# Insoladora.net
KiCad netlist of a schematic drawn in Altium Designer
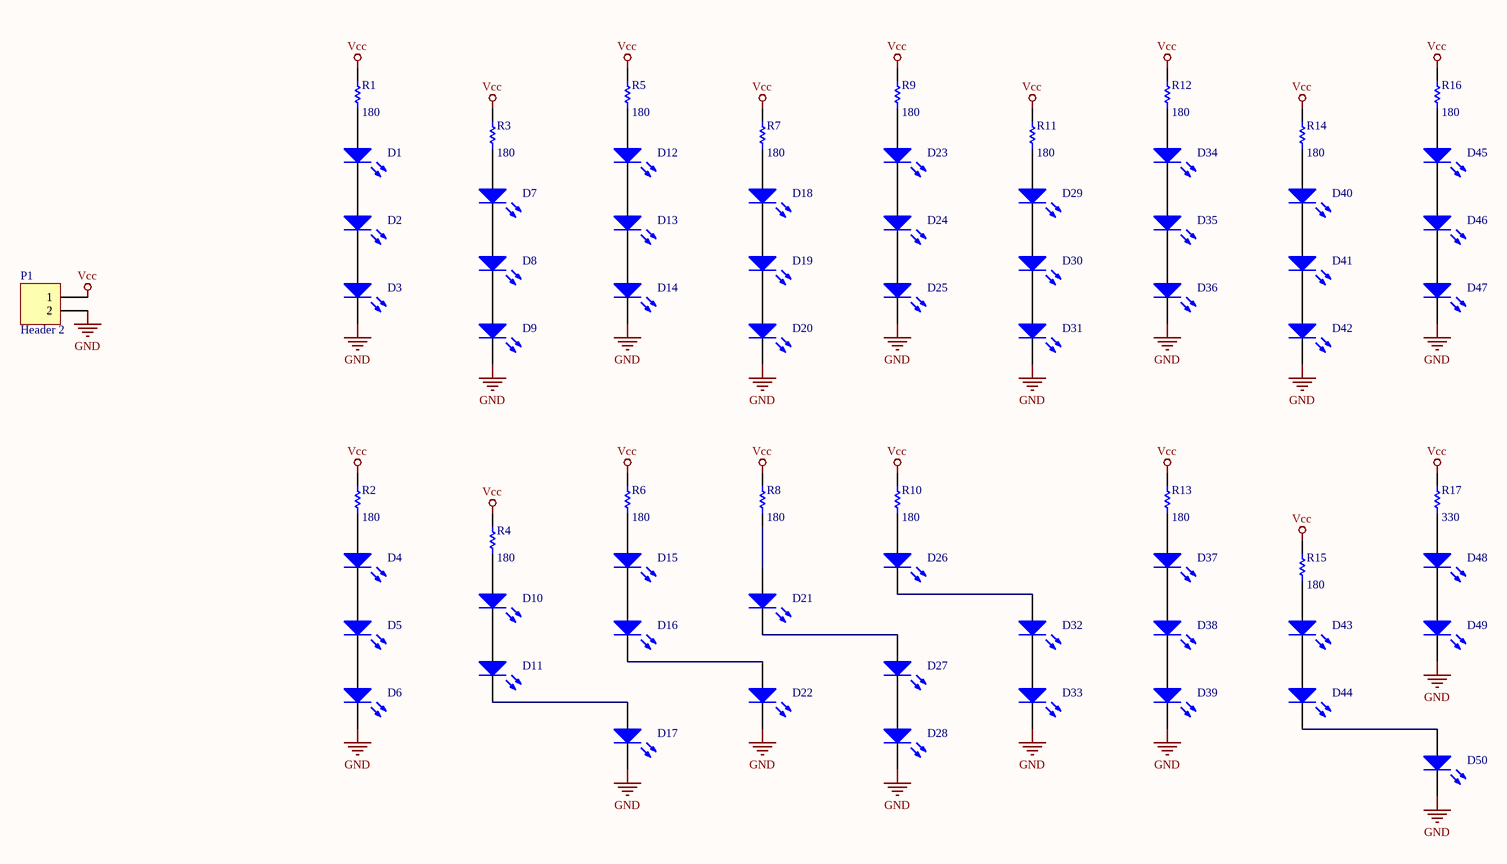
[diagram p0: Insoladora.SchDoc]

(export (version "E")
  (design (tool "Eeschema 10.0.6"))
  (components
    (comp (ref "D1")
      (value "LEDUV")
      (footprint "LED Clear")
      (description "LED UV 5mm 25° apertura")
      (fields (field (name "PUBLISHER") "Altium Limited"))
      (libsource (lib "Miscellaneous Devices") (part "LED2"))
    )
    (comp (ref "D2")
      (value "LEDUV")
      (footprint "LED Clear")
      (description "LED UV 5mm 25° apertura")
      (fields (field (name "PUBLISHER") "Altium Limited"))
      (libsource (lib "Miscellaneous Devices") (part "LED2"))
    )
    (comp (ref "D3")
      (value "LEDUV")
      (footprint "LED Clear")
      (description "LED UV 5mm 25° apertura")
      (fields (field (name "PUBLISHER") "Altium Limited"))
      (libsource (lib "Miscellaneous Devices") (part "LED2"))
    )
    (comp (ref "D4")
      (value "LEDUV")
      (footprint "LED Clear")
      (description "LED UV 5mm 25° apertura")
      (fields (field (name "PUBLISHER") "Altium Limited"))
      (libsource (lib "Miscellaneous Devices") (part "LED2"))
    )
    (comp (ref "D5")
      (value "LEDUV")
      (footprint "LED Clear")
      (description "LED UV 5mm 25° apertura")
      (fields (field (name "PUBLISHER") "Altium Limited"))
      (libsource (lib "Miscellaneous Devices") (part "LED2"))
    )
    (comp (ref "D6")
      (value "LEDUV")
      (footprint "LED Clear")
      (description "LED UV 5mm 25° apertura")
      (fields (field (name "PUBLISHER") "Altium Limited"))
      (libsource (lib "Miscellaneous Devices") (part "LED2"))
    )
    (comp (ref "D7")
      (value "LEDUV")
      (footprint "LED Clear")
      (description "LED UV 5mm 25° apertura")
      (fields (field (name "PUBLISHER") "Altium Limited"))
      (libsource (lib "Miscellaneous Devices") (part "LED2"))
    )
    (comp (ref "D8")
      (value "LEDUV")
      (footprint "LED Clear")
      (description "LED UV 5mm 25° apertura")
      (fields (field (name "PUBLISHER") "Altium Limited"))
      (libsource (lib "Miscellaneous Devices") (part "LED2"))
    )
    (comp (ref "D9")
      (value "LEDUV")
      (footprint "LED Clear")
      (description "LED UV 5mm 25° apertura")
      (fields (field (name "PUBLISHER") "Altium Limited"))
      (libsource (lib "Miscellaneous Devices") (part "LED2"))
    )
    (comp (ref "D10")
      (value "LEDUV")
      (footprint "LED Clear")
      (description "LED UV 5mm 25° apertura")
      (fields (field (name "PUBLISHER") "Altium Limited"))
      (libsource (lib "Miscellaneous Devices") (part "LED2"))
    )
    (comp (ref "D11")
      (value "LEDUV")
      (footprint "LED Clear")
      (description "LED UV 5mm 25° apertura")
      (fields (field (name "PUBLISHER") "Altium Limited"))
      (libsource (lib "Miscellaneous Devices") (part "LED2"))
    )
    (comp (ref "D12")
      (value "LEDUV")
      (footprint "LED Clear")
      (description "LED UV 5mm 25° apertura")
      (fields (field (name "PUBLISHER") "Altium Limited"))
      (libsource (lib "Miscellaneous Devices") (part "LED2"))
    )
    (comp (ref "D13")
      (value "LEDUV")
      (footprint "LED Clear")
      (description "LED UV 5mm 25° apertura")
      (fields (field (name "PUBLISHER") "Altium Limited"))
      (libsource (lib "Miscellaneous Devices") (part "LED2"))
    )
    (comp (ref "D14")
      (value "LEDUV")
      (footprint "LED Clear")
      (description "LED UV 5mm 25° apertura")
      (fields (field (name "PUBLISHER") "Altium Limited"))
      (libsource (lib "Miscellaneous Devices") (part "LED2"))
    )
    (comp (ref "D15")
      (value "LEDUV")
      (footprint "LED Clear")
      (description "LED UV 5mm 25° apertura")
      (fields (field (name "PUBLISHER") "Altium Limited"))
      (libsource (lib "Miscellaneous Devices") (part "LED2"))
    )
    (comp (ref "D16")
      (value "LEDUV")
      (footprint "LED Clear")
      (description "LED UV 5mm 25° apertura")
      (fields (field (name "PUBLISHER") "Altium Limited"))
      (libsource (lib "Miscellaneous Devices") (part "LED2"))
    )
    (comp (ref "D17")
      (value "LEDUV")
      (footprint "LED Clear")
      (description "LED UV 5mm 25° apertura")
      (fields (field (name "PUBLISHER") "Altium Limited"))
      (libsource (lib "Miscellaneous Devices") (part "LED2"))
    )
    (comp (ref "D18")
      (value "LEDUV")
      (footprint "LED Clear")
      (description "LED UV 5mm 25° apertura")
      (fields (field (name "PUBLISHER") "Altium Limited"))
      (libsource (lib "Miscellaneous Devices") (part "LED2"))
    )
    (comp (ref "D19")
      (value "LEDUV")
      (footprint "LED Clear")
      (description "LED UV 5mm 25° apertura")
      (fields (field (name "PUBLISHER") "Altium Limited"))
      (libsource (lib "Miscellaneous Devices") (part "LED2"))
    )
    (comp (ref "D20")
      (value "LEDUV")
      (footprint "LED Clear")
      (description "LED UV 5mm 25° apertura")
      (fields (field (name "PUBLISHER") "Altium Limited"))
      (libsource (lib "Miscellaneous Devices") (part "LED2"))
    )
    (comp (ref "D21")
      (value "LEDUV")
      (footprint "LED Clear")
      (description "LED UV 5mm 25° apertura")
      (fields (field (name "PUBLISHER") "Altium Limited"))
      (libsource (lib "Miscellaneous Devices") (part "LED2"))
    )
    (comp (ref "D22")
      (value "LEDUV")
      (footprint "LED Clear")
      (description "LED UV 5mm 25° apertura")
      (fields (field (name "PUBLISHER") "Altium Limited"))
      (libsource (lib "Miscellaneous Devices") (part "LED2"))
    )
    (comp (ref "D23")
      (value "LEDUV")
      (footprint "LED Clear")
      (description "LED UV 5mm 25° apertura")
      (fields (field (name "PUBLISHER") "Altium Limited"))
      (libsource (lib "Miscellaneous Devices") (part "LED2"))
    )
    (comp (ref "D24")
      (value "LEDUV")
      (footprint "LED Clear")
      (description "LED UV 5mm 25° apertura")
      (fields (field (name "PUBLISHER") "Altium Limited"))
      (libsource (lib "Miscellaneous Devices") (part "LED2"))
    )
    (comp (ref "D25")
      (value "LEDUV")
      (footprint "LED Clear")
      (description "LED UV 5mm 25° apertura")
      (fields (field (name "PUBLISHER") "Altium Limited"))
      (libsource (lib "Miscellaneous Devices") (part "LED2"))
    )
    (comp (ref "D26")
      (value "LEDUV")
      (footprint "LED Clear")
      (description "LED UV 5mm 25° apertura")
      (fields (field (name "PUBLISHER") "Altium Limited"))
      (libsource (lib "Miscellaneous Devices") (part "LED2"))
    )
    (comp (ref "D27")
      (value "LEDUV")
      (footprint "LED Clear")
      (description "LED UV 5mm 25° apertura")
      (fields (field (name "PUBLISHER") "Altium Limited"))
      (libsource (lib "Miscellaneous Devices") (part "LED2"))
    )
    (comp (ref "D28")
      (value "LEDUV")
      (footprint "LED Clear")
      (description "LED UV 5mm 25° apertura")
      (fields (field (name "PUBLISHER") "Altium Limited"))
      (libsource (lib "Miscellaneous Devices") (part "LED2"))
    )
    (comp (ref "D29")
      (value "LEDUV")
      (footprint "LED Clear")
      (description "LED UV 5mm 25° apertura")
      (fields (field (name "PUBLISHER") "Altium Limited"))
      (libsource (lib "Miscellaneous Devices") (part "LED2"))
    )
    (comp (ref "D30")
      (value "LEDUV")
      (footprint "LED Clear")
      (description "LED UV 5mm 25° apertura")
      (fields (field (name "PUBLISHER") "Altium Limited"))
      (libsource (lib "Miscellaneous Devices") (part "LED2"))
    )
    (comp (ref "D31")
      (value "LEDUV")
      (footprint "LED Clear")
      (description "LED UV 5mm 25° apertura")
      (fields (field (name "PUBLISHER") "Altium Limited"))
      (libsource (lib "Miscellaneous Devices") (part "LED2"))
    )
    (comp (ref "D32")
      (value "LEDUV")
      (footprint "LED Clear")
      (description "LED UV 5mm 25° apertura")
      (fields (field (name "PUBLISHER") "Altium Limited"))
      (libsource (lib "Miscellaneous Devices") (part "LED2"))
    )
    (comp (ref "D33")
      (value "LEDUV")
      (footprint "LED Clear")
      (description "LED UV 5mm 25° apertura")
      (fields (field (name "PUBLISHER") "Altium Limited"))
      (libsource (lib "Miscellaneous Devices") (part "LED2"))
    )
    (comp (ref "D34")
      (value "LEDUV")
      (footprint "LED Clear")
      (description "LED UV 5mm 25° apertura")
      (fields (field (name "PUBLISHER") "Altium Limited"))
      (libsource (lib "Miscellaneous Devices") (part "LED2"))
    )
    (comp (ref "D35")
      (value "LEDUV")
      (footprint "LED Clear")
      (description "LED UV 5mm 25° apertura")
      (fields (field (name "PUBLISHER") "Altium Limited"))
      (libsource (lib "Miscellaneous Devices") (part "LED2"))
    )
    (comp (ref "D36")
      (value "LEDUV")
      (footprint "LED Clear")
      (description "LED UV 5mm 25° apertura")
      (fields (field (name "PUBLISHER") "Altium Limited"))
      (libsource (lib "Miscellaneous Devices") (part "LED2"))
    )
    (comp (ref "D37")
      (value "LEDUV")
      (footprint "LED Clear")
      (description "LED UV 5mm 25° apertura")
      (fields (field (name "PUBLISHER") "Altium Limited"))
      (libsource (lib "Miscellaneous Devices") (part "LED2"))
    )
    (comp (ref "D38")
      (value "LEDUV")
      (footprint "LED Clear")
      (description "LED UV 5mm 25° apertura")
      (fields (field (name "PUBLISHER") "Altium Limited"))
      (libsource (lib "Miscellaneous Devices") (part "LED2"))
    )
    (comp (ref "D39")
      (value "LEDUV")
      (footprint "LED Clear")
      (description "LED UV 5mm 25° apertura")
      (fields (field (name "PUBLISHER") "Altium Limited"))
      (libsource (lib "Miscellaneous Devices") (part "LED2"))
    )
    (comp (ref "D40")
      (value "LEDUV")
      (footprint "LED Clear")
      (description "LED UV 5mm 25° apertura")
      (fields (field (name "PUBLISHER") "Altium Limited"))
      (libsource (lib "Miscellaneous Devices") (part "LED2"))
    )
    (comp (ref "D41")
      (value "LEDUV")
      (footprint "LED Clear")
      (description "LED UV 5mm 25° apertura")
      (fields (field (name "PUBLISHER") "Altium Limited"))
      (libsource (lib "Miscellaneous Devices") (part "LED2"))
    )
    (comp (ref "D42")
      (value "LEDUV")
      (footprint "LED Clear")
      (description "LED UV 5mm 25° apertura")
      (fields (field (name "PUBLISHER") "Altium Limited"))
      (libsource (lib "Miscellaneous Devices") (part "LED2"))
    )
    (comp (ref "D43")
      (value "LEDUV")
      (footprint "LED Clear")
      (description "LED UV 5mm 25° apertura")
      (fields (field (name "PUBLISHER") "Altium Limited"))
      (libsource (lib "Miscellaneous Devices") (part "LED2"))
    )
    (comp (ref "D44")
      (value "LEDUV")
      (footprint "LED Clear")
      (description "LED UV 5mm 25° apertura")
      (fields (field (name "PUBLISHER") "Altium Limited"))
      (libsource (lib "Miscellaneous Devices") (part "LED2"))
    )
    (comp (ref "D45")
      (value "LEDUV")
      (footprint "LED Clear")
      (description "LED UV 5mm 25° apertura")
      (fields (field (name "PUBLISHER") "Altium Limited"))
      (libsource (lib "Miscellaneous Devices") (part "LED2"))
    )
    (comp (ref "D46")
      (value "LEDUV")
      (footprint "LED Clear")
      (description "LED UV 5mm 25° apertura")
      (fields (field (name "PUBLISHER") "Altium Limited"))
      (libsource (lib "Miscellaneous Devices") (part "LED2"))
    )
    (comp (ref "D47")
      (value "LEDUV")
      (footprint "LED Clear")
      (description "LED UV 5mm 25° apertura")
      (fields (field (name "PUBLISHER") "Altium Limited"))
      (libsource (lib "Miscellaneous Devices") (part "LED2"))
    )
    (comp (ref "D48")
      (value "LEDUV")
      (footprint "LED Clear")
      (description "LED UV 5mm 25° apertura")
      (fields (field (name "PUBLISHER") "Altium Limited"))
      (libsource (lib "Miscellaneous Devices") (part "LED2"))
    )
    (comp (ref "D49")
      (value "LEDUV")
      (footprint "LED Clear")
      (description "LED UV 5mm 25° apertura")
      (fields (field (name "PUBLISHER") "Altium Limited"))
      (libsource (lib "Miscellaneous Devices") (part "LED2"))
    )
    (comp (ref "D50")
      (value "LEDUV")
      (footprint "LED Clear")
      (description "LED UV 5mm 25° apertura")
      (fields (field (name "PUBLISHER") "Altium Limited"))
      (libsource (lib "Miscellaneous Devices") (part "LED2"))
    )
    (comp (ref "P1")
      (value "Header 2")
      (footprint "HEADER 2")
      (description "Header, 2-Pin")
      (fields (field (name "PUBLISHER") "Altium Limited"))
      (libsource (lib "Miscellaneous Connectors") (part "Header 2"))
    )
    (comp (ref "R1")
      (value "180")
      (description "Resistor")
      (fields (field (name "Comment") "Res1") (field (name "PUBLISHER") "Altium Limited"))
      (libsource (lib "Miscellaneous Devices") (part "Res1"))
    )
    (comp (ref "R2")
      (value "180")
      (description "Resistor")
      (fields (field (name "Comment") "Res1") (field (name "PUBLISHER") "Altium Limited"))
      (libsource (lib "Miscellaneous Devices") (part "Res1"))
    )
    (comp (ref "R3")
      (value "180")
      (description "Resistor")
      (fields (field (name "Comment") "Res1") (field (name "PUBLISHER") "Altium Limited"))
      (libsource (lib "Miscellaneous Devices") (part "Res1"))
    )
    (comp (ref "R4")
      (value "180")
      (description "Resistor")
      (fields (field (name "Comment") "Res1") (field (name "PUBLISHER") "Altium Limited"))
      (libsource (lib "Miscellaneous Devices") (part "Res1"))
    )
    (comp (ref "R5")
      (value "180")
      (description "Resistor")
      (fields (field (name "Comment") "Res1") (field (name "PUBLISHER") "Altium Limited"))
      (libsource (lib "Miscellaneous Devices") (part "Res1"))
    )
    (comp (ref "R6")
      (value "180")
      (description "Resistor")
      (fields (field (name "Comment") "Res1") (field (name "PUBLISHER") "Altium Limited"))
      (libsource (lib "Miscellaneous Devices") (part "Res1"))
    )
    (comp (ref "R7")
      (value "180")
      (description "Resistor")
      (fields (field (name "Comment") "Res1") (field (name "PUBLISHER") "Altium Limited"))
      (libsource (lib "Miscellaneous Devices") (part "Res1"))
    )
    (comp (ref "R8")
      (value "180")
      (description "Resistor")
      (fields (field (name "Comment") "Res1") (field (name "PUBLISHER") "Altium Limited"))
      (libsource (lib "Miscellaneous Devices") (part "Res1"))
    )
    (comp (ref "R9")
      (value "180")
      (description "Resistor")
      (fields (field (name "Comment") "Res1") (field (name "PUBLISHER") "Altium Limited"))
      (libsource (lib "Miscellaneous Devices") (part "Res1"))
    )
    (comp (ref "R10")
      (value "180")
      (description "Resistor")
      (fields (field (name "Comment") "Res1") (field (name "PUBLISHER") "Altium Limited"))
      (libsource (lib "Miscellaneous Devices") (part "Res1"))
    )
    (comp (ref "R11")
      (value "180")
      (description "Resistor")
      (fields (field (name "Comment") "Res1") (field (name "PUBLISHER") "Altium Limited"))
      (libsource (lib "Miscellaneous Devices") (part "Res1"))
    )
    (comp (ref "R12")
      (value "180")
      (description "Resistor")
      (fields (field (name "Comment") "Res1") (field (name "PUBLISHER") "Altium Limited"))
      (libsource (lib "Miscellaneous Devices") (part "Res1"))
    )
    (comp (ref "R13")
      (value "180")
      (description "Resistor")
      (fields (field (name "Comment") "Res1") (field (name "PUBLISHER") "Altium Limited"))
      (libsource (lib "Miscellaneous Devices") (part "Res1"))
    )
    (comp (ref "R14")
      (value "180")
      (description "Resistor")
      (fields (field (name "Comment") "Res1") (field (name "PUBLISHER") "Altium Limited"))
      (libsource (lib "Miscellaneous Devices") (part "Res1"))
    )
    (comp (ref "R15")
      (value "180")
      (description "Resistor")
      (fields (field (name "Comment") "Res1") (field (name "PUBLISHER") "Altium Limited"))
      (libsource (lib "Miscellaneous Devices") (part "Res1"))
    )
    (comp (ref "R16")
      (value "180")
      (description "Resistor")
      (fields (field (name "Comment") "Res1") (field (name "PUBLISHER") "Altium Limited"))
      (libsource (lib "Miscellaneous Devices") (part "Res1"))
    )
    (comp (ref "R17")
      (value "330")
      (description "Resistor")
      (fields (field (name "Comment") "Res1") (field (name "PUBLISHER") "Altium Limited"))
      (libsource (lib "Miscellaneous Devices") (part "Res1"))
    )
  )
  (nets
    (net (code "1") (name "GND") (class "Default")
      (node (ref "D14") (pin "2") (pinfunction "K_2") (pintype "passive"))
      (node (ref "D17") (pin "2") (pinfunction "K_2") (pintype "passive"))
      (node (ref "D20") (pin "2") (pinfunction "K_2") (pintype "passive"))
      (node (ref "D22") (pin "2") (pinfunction "K_2") (pintype "passive"))
      (node (ref "D25") (pin "2") (pinfunction "K_2") (pintype "passive"))
      (node (ref "D28") (pin "2") (pinfunction "K_2") (pintype "passive"))
      (node (ref "D3") (pin "2") (pinfunction "K_2") (pintype "passive"))
      (node (ref "D31") (pin "2") (pinfunction "K_2") (pintype "passive"))
      (node (ref "D33") (pin "2") (pinfunction "K_2") (pintype "passive"))
      (node (ref "D36") (pin "2") (pinfunction "K_2") (pintype "passive"))
      (node (ref "D39") (pin "2") (pinfunction "K_2") (pintype "passive"))
      (node (ref "D42") (pin "2") (pinfunction "K_2") (pintype "passive"))
      (node (ref "D47") (pin "2") (pinfunction "K_2") (pintype "passive"))
      (node (ref "D49") (pin "2") (pinfunction "K_2") (pintype "passive"))
      (node (ref "D50") (pin "2") (pinfunction "K_2") (pintype "passive"))
      (node (ref "D6") (pin "2") (pinfunction "K_2") (pintype "passive"))
      (node (ref "D9") (pin "2") (pinfunction "K_2") (pintype "passive"))
      (node (ref "P1") (pin "2") (pinfunction "2_2") (pintype "passive"))
    )
    (net (code "2") (name "Net-(D1-A)") (class "Default")
      (node (ref "D1") (pin "1") (pinfunction "A_1") (pintype "passive"))
      (node (ref "R1") (pin "1") (pinfunction "1_1") (pintype "passive"))
    )
    (net (code "3") (name "Net-(D1-K)") (class "Default")
      (node (ref "D1") (pin "2") (pinfunction "K_2") (pintype "passive"))
      (node (ref "D2") (pin "1") (pinfunction "A_1") (pintype "passive"))
    )
    (net (code "4") (name "Net-(D2-K)") (class "Default")
      (node (ref "D2") (pin "2") (pinfunction "K_2") (pintype "passive"))
      (node (ref "D3") (pin "1") (pinfunction "A_1") (pintype "passive"))
    )
    (net (code "5") (name "Net-(D4-A)") (class "Default")
      (node (ref "D4") (pin "1") (pinfunction "A_1") (pintype "passive"))
      (node (ref "R2") (pin "1") (pinfunction "1_1") (pintype "passive"))
    )
    (net (code "6") (name "Net-(D4-K)") (class "Default")
      (node (ref "D4") (pin "2") (pinfunction "K_2") (pintype "passive"))
      (node (ref "D5") (pin "1") (pinfunction "A_1") (pintype "passive"))
    )
    (net (code "7") (name "Net-(D5-K)") (class "Default")
      (node (ref "D5") (pin "2") (pinfunction "K_2") (pintype "passive"))
      (node (ref "D6") (pin "1") (pinfunction "A_1") (pintype "passive"))
    )
    (net (code "8") (name "Net-(D7-A)") (class "Default")
      (node (ref "D7") (pin "1") (pinfunction "A_1") (pintype "passive"))
      (node (ref "R3") (pin "1") (pinfunction "1_1") (pintype "passive"))
    )
    (net (code "9") (name "Net-(D7-K)") (class "Default")
      (node (ref "D7") (pin "2") (pinfunction "K_2") (pintype "passive"))
      (node (ref "D8") (pin "1") (pinfunction "A_1") (pintype "passive"))
    )
    (net (code "10") (name "Net-(D8-K)") (class "Default")
      (node (ref "D8") (pin "2") (pinfunction "K_2") (pintype "passive"))
      (node (ref "D9") (pin "1") (pinfunction "A_1") (pintype "passive"))
    )
    (net (code "11") (name "Net-(D10-A)") (class "Default")
      (node (ref "D10") (pin "1") (pinfunction "A_1") (pintype "passive"))
      (node (ref "R4") (pin "1") (pinfunction "1_1") (pintype "passive"))
    )
    (net (code "12") (name "Net-(D10-K)") (class "Default")
      (node (ref "D10") (pin "2") (pinfunction "K_2") (pintype "passive"))
      (node (ref "D11") (pin "1") (pinfunction "A_1") (pintype "passive"))
    )
    (net (code "13") (name "Net-(D11-K)") (class "Default")
      (node (ref "D11") (pin "2") (pinfunction "K_2") (pintype "passive"))
      (node (ref "D17") (pin "1") (pinfunction "A_1") (pintype "passive"))
    )
    (net (code "14") (name "Net-(D12-A)") (class "Default")
      (node (ref "D12") (pin "1") (pinfunction "A_1") (pintype "passive"))
      (node (ref "R5") (pin "1") (pinfunction "1_1") (pintype "passive"))
    )
    (net (code "15") (name "Net-(D12-K)") (class "Default")
      (node (ref "D12") (pin "2") (pinfunction "K_2") (pintype "passive"))
      (node (ref "D13") (pin "1") (pinfunction "A_1") (pintype "passive"))
    )
    (net (code "16") (name "Net-(D13-K)") (class "Default")
      (node (ref "D13") (pin "2") (pinfunction "K_2") (pintype "passive"))
      (node (ref "D14") (pin "1") (pinfunction "A_1") (pintype "passive"))
    )
    (net (code "17") (name "Net-(D15-A)") (class "Default")
      (node (ref "D15") (pin "1") (pinfunction "A_1") (pintype "passive"))
      (node (ref "R6") (pin "1") (pinfunction "1_1") (pintype "passive"))
    )
    (net (code "18") (name "Net-(D15-K)") (class "Default")
      (node (ref "D15") (pin "2") (pinfunction "K_2") (pintype "passive"))
      (node (ref "D16") (pin "1") (pinfunction "A_1") (pintype "passive"))
    )
    (net (code "19") (name "Net-(D16-K)") (class "Default")
      (node (ref "D16") (pin "2") (pinfunction "K_2") (pintype "passive"))
      (node (ref "D22") (pin "1") (pinfunction "A_1") (pintype "passive"))
    )
    (net (code "20") (name "Net-(D18-A)") (class "Default")
      (node (ref "D18") (pin "1") (pinfunction "A_1") (pintype "passive"))
      (node (ref "R7") (pin "1") (pinfunction "1_1") (pintype "passive"))
    )
    (net (code "21") (name "Net-(D18-K)") (class "Default")
      (node (ref "D18") (pin "2") (pinfunction "K_2") (pintype "passive"))
      (node (ref "D19") (pin "1") (pinfunction "A_1") (pintype "passive"))
    )
    (net (code "22") (name "Net-(D19-K)") (class "Default")
      (node (ref "D19") (pin "2") (pinfunction "K_2") (pintype "passive"))
      (node (ref "D20") (pin "1") (pinfunction "A_1") (pintype "passive"))
    )
    (net (code "23") (name "Net-(D21-A)") (class "Default")
      (node (ref "D21") (pin "1") (pinfunction "A_1") (pintype "passive"))
      (node (ref "R8") (pin "1") (pinfunction "1_1") (pintype "passive"))
    )
    (net (code "24") (name "Net-(D21-K)") (class "Default")
      (node (ref "D21") (pin "2") (pinfunction "K_2") (pintype "passive"))
      (node (ref "D27") (pin "1") (pinfunction "A_1") (pintype "passive"))
    )
    (net (code "25") (name "Net-(D23-A)") (class "Default")
      (node (ref "D23") (pin "1") (pinfunction "A_1") (pintype "passive"))
      (node (ref "R9") (pin "1") (pinfunction "1_1") (pintype "passive"))
    )
    (net (code "26") (name "Net-(D23-K)") (class "Default")
      (node (ref "D23") (pin "2") (pinfunction "K_2") (pintype "passive"))
      (node (ref "D24") (pin "1") (pinfunction "A_1") (pintype "passive"))
    )
    (net (code "27") (name "Net-(D24-K)") (class "Default")
      (node (ref "D24") (pin "2") (pinfunction "K_2") (pintype "passive"))
      (node (ref "D25") (pin "1") (pinfunction "A_1") (pintype "passive"))
    )
    (net (code "28") (name "Net-(D26-A)") (class "Default")
      (node (ref "D26") (pin "1") (pinfunction "A_1") (pintype "passive"))
      (node (ref "R10") (pin "1") (pinfunction "1_1") (pintype "passive"))
    )
    (net (code "29") (name "Net-(D26-K)") (class "Default")
      (node (ref "D26") (pin "2") (pinfunction "K_2") (pintype "passive"))
      (node (ref "D32") (pin "1") (pinfunction "A_1") (pintype "passive"))
    )
    (net (code "30") (name "Net-(D27-K)") (class "Default")
      (node (ref "D27") (pin "2") (pinfunction "K_2") (pintype "passive"))
      (node (ref "D28") (pin "1") (pinfunction "A_1") (pintype "passive"))
    )
    (net (code "31") (name "Net-(D29-A)") (class "Default")
      (node (ref "D29") (pin "1") (pinfunction "A_1") (pintype "passive"))
      (node (ref "R11") (pin "1") (pinfunction "1_1") (pintype "passive"))
    )
    (net (code "32") (name "Net-(D29-K)") (class "Default")
      (node (ref "D29") (pin "2") (pinfunction "K_2") (pintype "passive"))
      (node (ref "D30") (pin "1") (pinfunction "A_1") (pintype "passive"))
    )
    (net (code "33") (name "Net-(D30-K)") (class "Default")
      (node (ref "D30") (pin "2") (pinfunction "K_2") (pintype "passive"))
      (node (ref "D31") (pin "1") (pinfunction "A_1") (pintype "passive"))
    )
    (net (code "34") (name "Net-(D32-K)") (class "Default")
      (node (ref "D32") (pin "2") (pinfunction "K_2") (pintype "passive"))
      (node (ref "D33") (pin "1") (pinfunction "A_1") (pintype "passive"))
    )
    (net (code "35") (name "Net-(D34-A)") (class "Default")
      (node (ref "D34") (pin "1") (pinfunction "A_1") (pintype "passive"))
      (node (ref "R12") (pin "1") (pinfunction "1_1") (pintype "passive"))
    )
    (net (code "36") (name "Net-(D34-K)") (class "Default")
      (node (ref "D34") (pin "2") (pinfunction "K_2") (pintype "passive"))
      (node (ref "D35") (pin "1") (pinfunction "A_1") (pintype "passive"))
    )
    (net (code "37") (name "Net-(D35-K)") (class "Default")
      (node (ref "D35") (pin "2") (pinfunction "K_2") (pintype "passive"))
      (node (ref "D36") (pin "1") (pinfunction "A_1") (pintype "passive"))
    )
    (net (code "38") (name "Net-(D37-A)") (class "Default")
      (node (ref "D37") (pin "1") (pinfunction "A_1") (pintype "passive"))
      (node (ref "R13") (pin "1") (pinfunction "1_1") (pintype "passive"))
    )
    (net (code "39") (name "Net-(D37-K)") (class "Default")
      (node (ref "D37") (pin "2") (pinfunction "K_2") (pintype "passive"))
      (node (ref "D38") (pin "1") (pinfunction "A_1") (pintype "passive"))
    )
    (net (code "40") (name "Net-(D38-K)") (class "Default")
      (node (ref "D38") (pin "2") (pinfunction "K_2") (pintype "passive"))
      (node (ref "D39") (pin "1") (pinfunction "A_1") (pintype "passive"))
    )
    (net (code "41") (name "Net-(D40-A)") (class "Default")
      (node (ref "D40") (pin "1") (pinfunction "A_1") (pintype "passive"))
      (node (ref "R14") (pin "1") (pinfunction "1_1") (pintype "passive"))
    )
    (net (code "42") (name "Net-(D40-K)") (class "Default")
      (node (ref "D40") (pin "2") (pinfunction "K_2") (pintype "passive"))
      (node (ref "D41") (pin "1") (pinfunction "A_1") (pintype "passive"))
    )
    (net (code "43") (name "Net-(D41-K)") (class "Default")
      (node (ref "D41") (pin "2") (pinfunction "K_2") (pintype "passive"))
      (node (ref "D42") (pin "1") (pinfunction "A_1") (pintype "passive"))
    )
    (net (code "44") (name "Net-(D43-A)") (class "Default")
      (node (ref "D43") (pin "1") (pinfunction "A_1") (pintype "passive"))
      (node (ref "R15") (pin "1") (pinfunction "1_1") (pintype "passive"))
    )
    (net (code "45") (name "Net-(D43-K)") (class "Default")
      (node (ref "D43") (pin "2") (pinfunction "K_2") (pintype "passive"))
      (node (ref "D44") (pin "1") (pinfunction "A_1") (pintype "passive"))
    )
    (net (code "46") (name "Net-(D44-K)") (class "Default")
      (node (ref "D44") (pin "2") (pinfunction "K_2") (pintype "passive"))
      (node (ref "D50") (pin "1") (pinfunction "A_1") (pintype "passive"))
    )
    (net (code "47") (name "Net-(D45-A)") (class "Default")
      (node (ref "D45") (pin "1") (pinfunction "A_1") (pintype "passive"))
      (node (ref "R16") (pin "1") (pinfunction "1_1") (pintype "passive"))
    )
    (net (code "48") (name "Net-(D45-K)") (class "Default")
      (node (ref "D45") (pin "2") (pinfunction "K_2") (pintype "passive"))
      (node (ref "D46") (pin "1") (pinfunction "A_1") (pintype "passive"))
    )
    (net (code "49") (name "Net-(D46-K)") (class "Default")
      (node (ref "D46") (pin "2") (pinfunction "K_2") (pintype "passive"))
      (node (ref "D47") (pin "1") (pinfunction "A_1") (pintype "passive"))
    )
    (net (code "50") (name "Net-(D48-A)") (class "Default")
      (node (ref "D48") (pin "1") (pinfunction "A_1") (pintype "passive"))
      (node (ref "R17") (pin "1") (pinfunction "1_1") (pintype "passive"))
    )
    (net (code "51") (name "Net-(D48-K)") (class "Default")
      (node (ref "D48") (pin "2") (pinfunction "K_2") (pintype "passive"))
      (node (ref "D49") (pin "1") (pinfunction "A_1") (pintype "passive"))
    )
    (net (code "52") (name "Vcc") (class "Default")
      (node (ref "P1") (pin "1") (pinfunction "1_1") (pintype "passive"))
      (node (ref "R1") (pin "2") (pinfunction "2_2") (pintype "passive"))
      (node (ref "R10") (pin "2") (pinfunction "2_2") (pintype "passive"))
      (node (ref "R11") (pin "2") (pinfunction "2_2") (pintype "passive"))
      (node (ref "R12") (pin "2") (pinfunction "2_2") (pintype "passive"))
      (node (ref "R13") (pin "2") (pinfunction "2_2") (pintype "passive"))
      (node (ref "R14") (pin "2") (pinfunction "2_2") (pintype "passive"))
      (node (ref "R15") (pin "2") (pinfunction "2_2") (pintype "passive"))
      (node (ref "R16") (pin "2") (pinfunction "2_2") (pintype "passive"))
      (node (ref "R17") (pin "2") (pinfunction "2_2") (pintype "passive"))
      (node (ref "R2") (pin "2") (pinfunction "2_2") (pintype "passive"))
      (node (ref "R3") (pin "2") (pinfunction "2_2") (pintype "passive"))
      (node (ref "R4") (pin "2") (pinfunction "2_2") (pintype "passive"))
      (node (ref "R5") (pin "2") (pinfunction "2_2") (pintype "passive"))
      (node (ref "R6") (pin "2") (pinfunction "2_2") (pintype "passive"))
      (node (ref "R7") (pin "2") (pinfunction "2_2") (pintype "passive"))
      (node (ref "R8") (pin "2") (pinfunction "2_2") (pintype "passive"))
      (node (ref "R9") (pin "2") (pinfunction "2_2") (pintype "passive"))
    )
  )
)
